# SCH5_Misc.net
KiCad netlist of a schematic drawn in Altium Designer
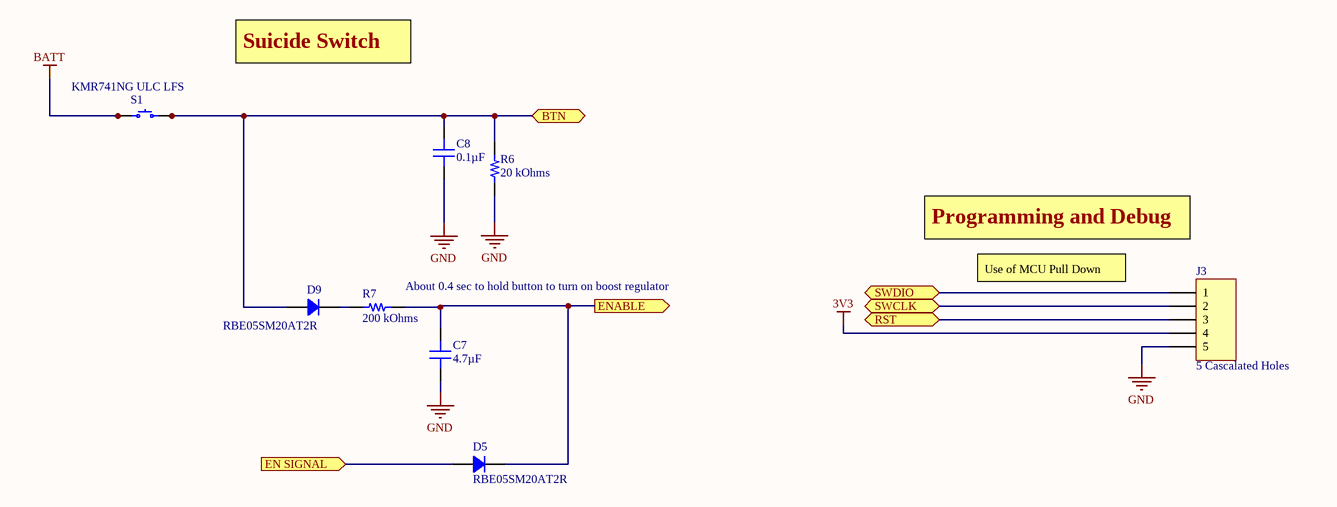
[diagram p0: SCH5_Misc.SchDoc]

(export (version "E")
  (design (tool "Eeschema 10.0.6"))
  (components
    (comp (ref "C7")
      (value "4.7µF")
      (footprint "CAP 0402_1005")
      (description "CAP CER 4.7UF 10V X5R 0402")
      (fields
        (field (name "PART NUMBER") "C1005X5R1A475K050BC")
        (field (name "MANUFACTURER") "TDK Corporation")
      )
      (libsource (lib "Celestial Altium Library - altium_library") (part "Capacitor"))
    )
    (comp (ref "C8")
      (value "0.1µF")
      (footprint "CAP 0402_1005")
      (description "CAP CER 0.1UF 25V X5R 0402")
      (fields (field (name "PART NUMBER") "CC0402KRX5R8BB104") (field (name "MANUFACTURER") "Yageo"))
      (libsource (lib "Celestial Altium Library - altium_library") (part "Capacitor"))
    )
    (comp (ref "D5")
      (value "RBE05SM20AT2R")
      (footprint "SOD-523")
      (description "DIODE SCHOTTKY 20V 500MA EMD2")
      (fields (field (name "MANUFACTURER") "Rohm Semiconductor"))
      (libsource (lib "Celestial Altium Library - altium_library") (part "Diode"))
    )
    (comp (ref "D9")
      (value "RBE05SM20AT2R")
      (footprint "SOD-523")
      (description "DIODE SCHOTTKY 20V 500MA EMD2")
      (fields (field (name "MANUFACTURER") "Rohm Semiconductor"))
      (libsource (lib "Celestial Altium Library - altium_library") (part "Diode"))
    )
    (comp (ref "J3")
      (value "5 Cascalated Holes")
      (footprint "Cascalated Holes")
      (fields (field (name "PUBLISHER") "Altium Limited"))
      (libsource (lib "SCH_Lib") (part "Cascalated Holes"))
    )
    (comp (ref "R6")
      (value "20 kOhms")
      (footprint "RES 0402_1005")
      (description "RES SMD 20K OHM 0.5% 1/16W 0402")
      (fields (field (name "PART NUMBER") "RG1005P-203-D-T10") (field (name "MANUFACTURER") "Susumu"))
      (libsource (lib "Celestial Altium Library - altium_library") (part "Resistor"))
    )
    (comp (ref "R7")
      (value "200 kOhms")
      (footprint "RES 0402_1005")
      (description "RES SMD 200 KOHM 5% 1/5W 0402")
      (fields
        (field (name "PART NUMBER") "ERJ-PA2J204X")
        (field (name "MANUFACTURER") "Panasonic Electronic Components")
      )
      (libsource (lib "Celestial Altium Library - altium_library") (part "Resistor"))
    )
    (comp (ref "S1")
      (value "KMR741NG ULC LFS")
      (footprint "C&K KMR7")
      (description "SWITCH TACTILE SPST-NO 50MA 32V")
      (fields (field (name "MANUFACTURER") "C&K"))
      (libsource (lib "Celestial Altium Library - altium_library") (part "SPST-NO 4 PIN"))
    )
  )
  (nets
    (net (code "1") (name "/BTN") (class "Default")
      (node (ref "C8") (pin "2") (pinfunction "2_2") (pintype "passive"))
      (node (ref "D9") (pin "1") (pinfunction "1_1") (pintype "passive"))
      (node (ref "R6") (pin "2") (pinfunction "2_2") (pintype "passive"))
      (node (ref "S1") (pin "3") (pinfunction "3_3") (pintype "passive"))
      (node (ref "S1") (pin "4") (pinfunction "4_4") (pintype "passive"))
    )
    (net (code "2") (name "/EN SIGNAL") (class "Default")
      (node (ref "D5") (pin "1") (pinfunction "1_1") (pintype "passive"))
    )
    (net (code "3") (name "/ENABLE") (class "Default")
      (node (ref "C7") (pin "2") (pinfunction "2_2") (pintype "passive"))
      (node (ref "D5") (pin "2") (pinfunction "2_2") (pintype "passive"))
      (node (ref "R7") (pin "2") (pinfunction "2_2") (pintype "passive"))
    )
    (net (code "4") (name "/RST") (class "Default")
      (node (ref "J3") (pin "3") (pinfunction "3_3") (pintype "passive"))
    )
    (net (code "5") (name "/SWCLK") (class "Default")
      (node (ref "J3") (pin "2") (pinfunction "2_2") (pintype "passive"))
    )
    (net (code "6") (name "/SWDIO") (class "Default")
      (node (ref "J3") (pin "1") (pinfunction "1_1") (pintype "passive"))
    )
    (net (code "7") (name "3V3") (class "Default")
      (node (ref "J3") (pin "4") (pinfunction "4_4") (pintype "passive"))
    )
    (net (code "8") (name "BATT") (class "Default")
      (node (ref "S1") (pin "1") (pinfunction "1_1") (pintype "passive"))
      (node (ref "S1") (pin "2") (pinfunction "2_2") (pintype "passive"))
    )
    (net (code "9") (name "GND") (class "Default")
      (node (ref "C7") (pin "1") (pinfunction "1_1") (pintype "passive"))
      (node (ref "C8") (pin "1") (pinfunction "1_1") (pintype "passive"))
      (node (ref "J3") (pin "5") (pinfunction "5_5") (pintype "passive"))
      (node (ref "R6") (pin "1") (pinfunction "1_1") (pintype "passive"))
    )
    (net (code "10") (name "Net-(D9-Pad2)") (class "Default")
      (node (ref "D9") (pin "2") (pinfunction "2_2") (pintype "passive"))
      (node (ref "R7") (pin "1") (pinfunction "1_1") (pintype "passive"))
    )
  )
)
